# LedMatrix24.net
KiCad netlist of a schematic drawn in EAGLE
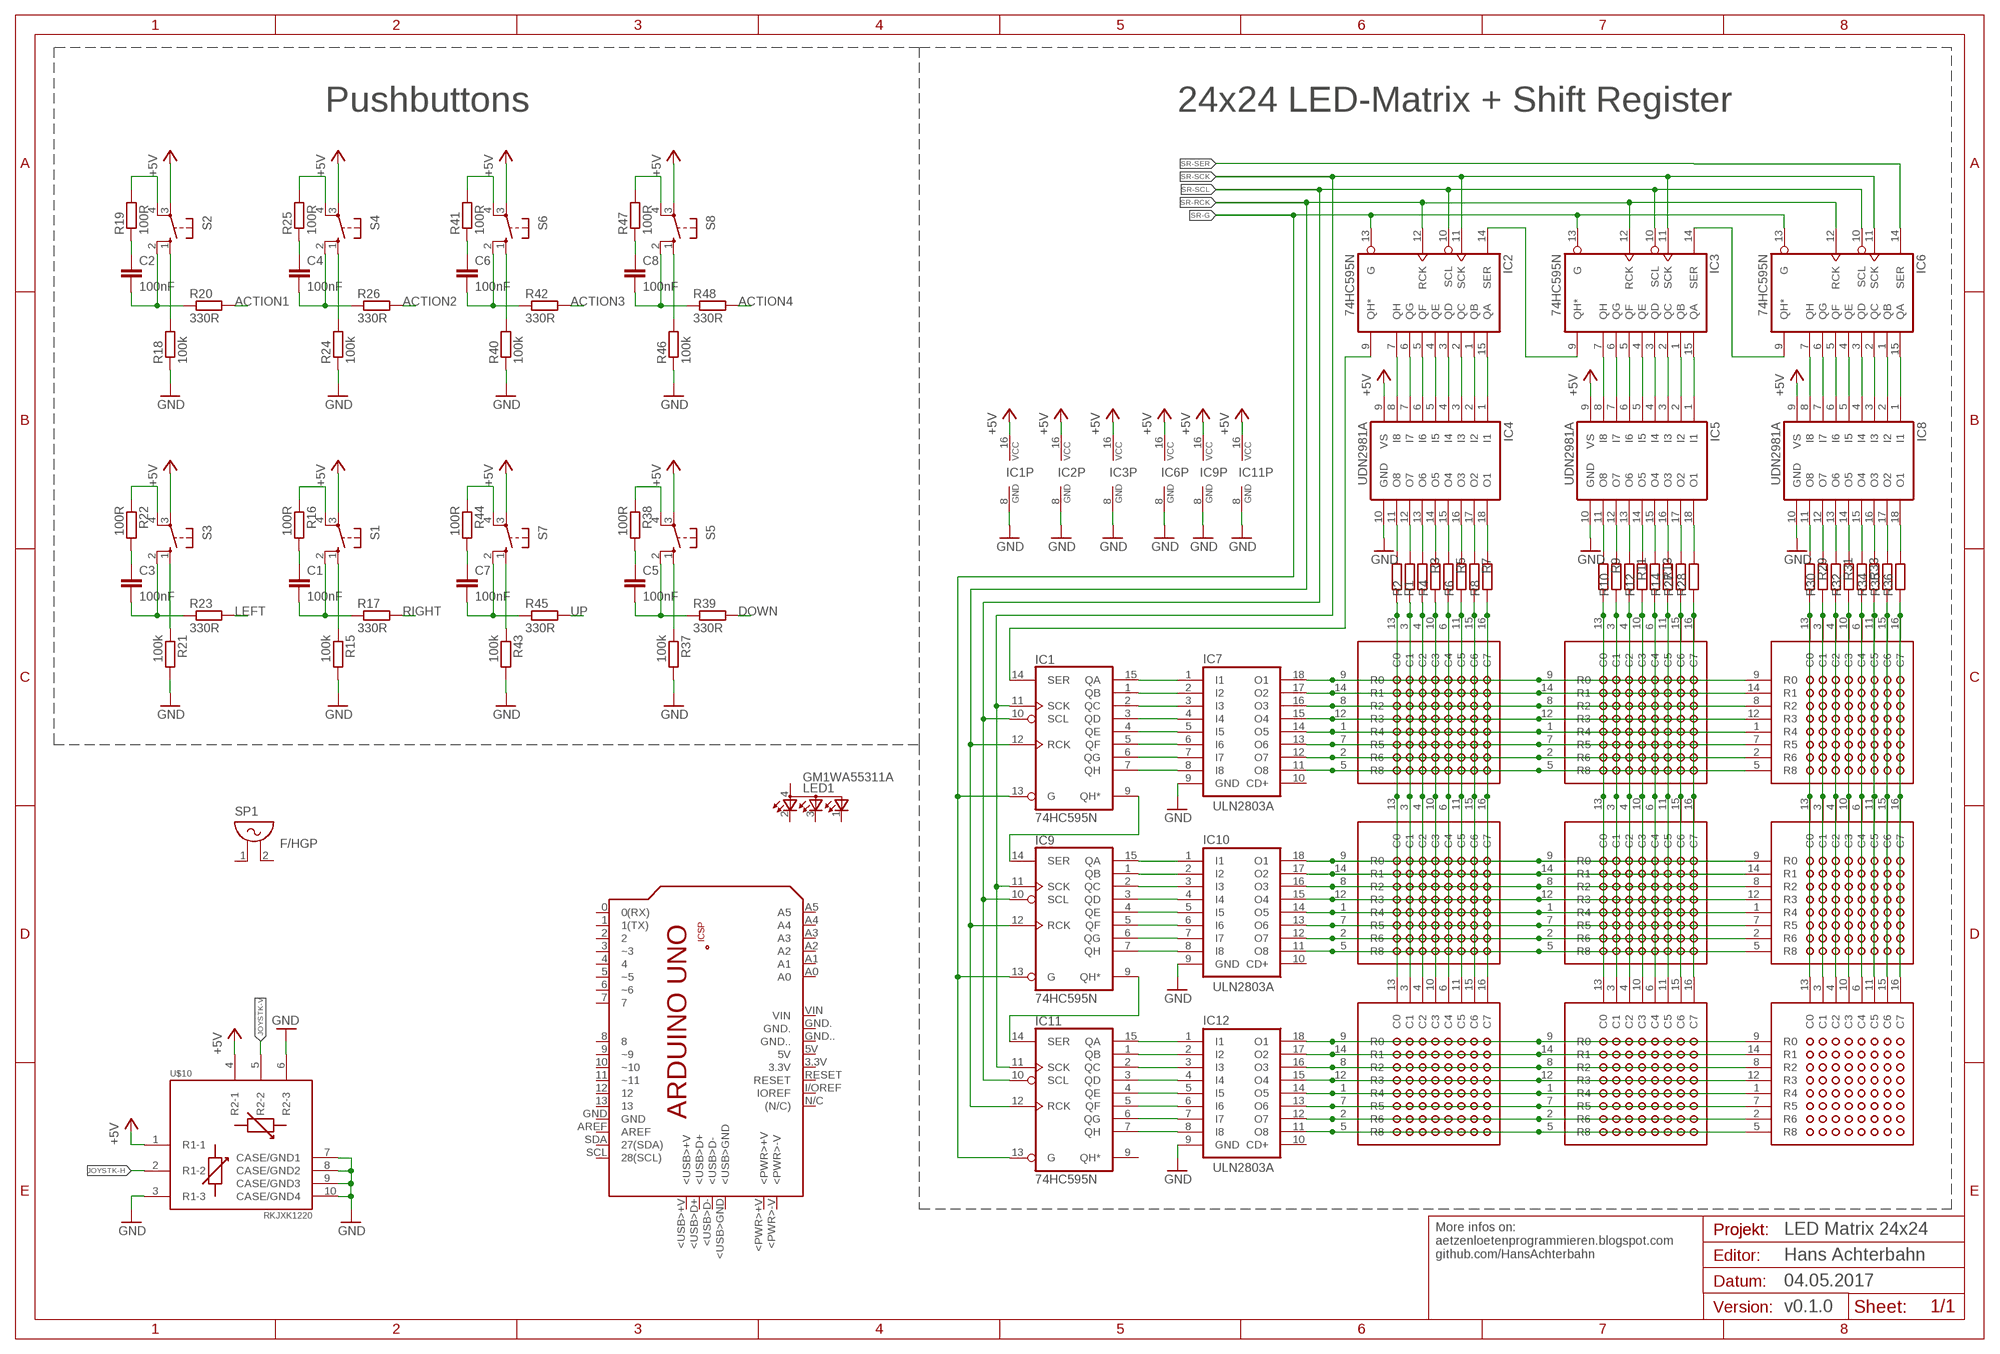
[diagram p0: schematic, sheet 1]

(export (version "E")
  (design (tool "Eeschema 10.0.6"))
  (components
    (comp (ref "C1")
      (value "100nF")
      (footprint "eagle-import:C0805")
      (libsource (lib "eagle-import") (part "C-EUC0805"))
    )
    (comp (ref "C2")
      (value "100nF")
      (footprint "eagle-import:C0805")
      (libsource (lib "eagle-import") (part "C-EUC0805"))
    )
    (comp (ref "C3")
      (value "100nF")
      (footprint "eagle-import:C0805")
      (libsource (lib "eagle-import") (part "C-EUC0805"))
    )
    (comp (ref "C4")
      (value "100nF")
      (footprint "eagle-import:C0805")
      (libsource (lib "eagle-import") (part "C-EUC0805"))
    )
    (comp (ref "C5")
      (value "100nF")
      (footprint "eagle-import:C0805")
      (libsource (lib "eagle-import") (part "C-EUC0805"))
    )
    (comp (ref "C6")
      (value "100nF")
      (footprint "eagle-import:C0805")
      (libsource (lib "eagle-import") (part "C-EUC0805"))
    )
    (comp (ref "C7")
      (value "100nF")
      (footprint "eagle-import:C0805")
      (libsource (lib "eagle-import") (part "C-EUC0805"))
    )
    (comp (ref "C8")
      (value "100nF")
      (footprint "eagle-import:C0805")
      (libsource (lib "eagle-import") (part "C-EUC0805"))
    )
    (comp (ref "IC1")
      (value "74HC595N")
      (footprint "eagle-import:DIL16")
      (libsource (lib "eagle-import") (part "74595NHC"))
    )
    (comp (ref "IC2")
      (value "74HC595N")
      (footprint "eagle-import:DIL16")
      (libsource (lib "eagle-import") (part "74595NHC"))
    )
    (comp (ref "IC3")
      (value "74HC595N")
      (footprint "eagle-import:DIL16")
      (libsource (lib "eagle-import") (part "74595NHC"))
    )
    (comp (ref "IC4")
      (value "UDN2981A")
      (footprint "eagle-import:DIL18")
      (libsource (lib "eagle-import") (part "UDN298A1"))
    )
    (comp (ref "IC5")
      (value "UDN2981A")
      (footprint "eagle-import:DIL18")
      (libsource (lib "eagle-import") (part "UDN298A1"))
    )
    (comp (ref "IC6")
      (value "74HC595N")
      (footprint "eagle-import:DIL16")
      (libsource (lib "eagle-import") (part "74595NHC"))
    )
    (comp (ref "IC7")
      (value "ULN2803A")
      (footprint "eagle-import:DIL18")
      (libsource (lib "eagle-import") (part "ULN2803A"))
    )
    (comp (ref "IC8")
      (value "UDN2981A")
      (footprint "eagle-import:DIL18")
      (libsource (lib "eagle-import") (part "UDN298A1"))
    )
    (comp (ref "IC9")
      (value "74HC595N")
      (footprint "eagle-import:DIL16")
      (libsource (lib "eagle-import") (part "74595NHC"))
    )
    (comp (ref "IC10")
      (value "ULN2803A")
      (footprint "eagle-import:DIL18")
      (libsource (lib "eagle-import") (part "ULN2803A"))
    )
    (comp (ref "IC11")
      (value "74HC595N")
      (footprint "eagle-import:DIL16")
      (libsource (lib "eagle-import") (part "74595NHC"))
    )
    (comp (ref "IC12")
      (value "ULN2803A")
      (footprint "eagle-import:DIL18")
      (libsource (lib "eagle-import") (part "ULN2803A"))
    )
    (comp (ref "LED1")
      (value "GM1WA55311A")
      (footprint "eagle-import:GM1WA55311A")
      (libsource (lib "eagle-import") (part "GM1WA55311A"))
    )
    (comp (ref "PCB1")
      (value "ARDUINO_UNO")
      (footprint "eagle-import:ARDUINO_UNO")
      (libsource (lib "eagle-import") (part "ARDUINO_UNO"))
    )
    (comp (ref "R1")
      (value "R-EU_0207/10")
      (footprint "eagle-import:0207_10")
      (libsource (lib "eagle-import") (part "R-EU_0207/10"))
    )
    (comp (ref "R2")
      (value "R-EU_0207/10")
      (footprint "eagle-import:0207_10")
      (libsource (lib "eagle-import") (part "R-EU_0207/10"))
    )
    (comp (ref "R3")
      (value "R-EU_0207/10")
      (footprint "eagle-import:0207_10")
      (libsource (lib "eagle-import") (part "R-EU_0207/10"))
    )
    (comp (ref "R4")
      (value "R-EU_0207/10")
      (footprint "eagle-import:0207_10")
      (libsource (lib "eagle-import") (part "R-EU_0207/10"))
    )
    (comp (ref "R5")
      (value "R-EU_0207/10")
      (footprint "eagle-import:0207_10")
      (libsource (lib "eagle-import") (part "R-EU_0207/10"))
    )
    (comp (ref "R6")
      (value "R-EU_0207/10")
      (footprint "eagle-import:0207_10")
      (libsource (lib "eagle-import") (part "R-EU_0207/10"))
    )
    (comp (ref "R7")
      (value "R-EU_0207/10")
      (footprint "eagle-import:0207_10")
      (libsource (lib "eagle-import") (part "R-EU_0207/10"))
    )
    (comp (ref "R8")
      (value "R-EU_0207/10")
      (footprint "eagle-import:0207_10")
      (libsource (lib "eagle-import") (part "R-EU_0207/10"))
    )
    (comp (ref "R9")
      (value "R-EU_0207/10")
      (footprint "eagle-import:0207_10")
      (libsource (lib "eagle-import") (part "R-EU_0207/10"))
    )
    (comp (ref "R10")
      (value "R-EU_0207/10")
      (footprint "eagle-import:0207_10")
      (libsource (lib "eagle-import") (part "R-EU_0207/10"))
    )
    (comp (ref "R11")
      (value "R-EU_0207/10")
      (footprint "eagle-import:0207_10")
      (libsource (lib "eagle-import") (part "R-EU_0207/10"))
    )
    (comp (ref "R12")
      (value "R-EU_0207/10")
      (footprint "eagle-import:0207_10")
      (libsource (lib "eagle-import") (part "R-EU_0207/10"))
    )
    (comp (ref "R13")
      (value "R-EU_0207/10")
      (footprint "eagle-import:0207_10")
      (libsource (lib "eagle-import") (part "R-EU_0207/10"))
    )
    (comp (ref "R14")
      (value "R-EU_0207/10")
      (footprint "eagle-import:0207_10")
      (libsource (lib "eagle-import") (part "R-EU_0207/10"))
    )
    (comp (ref "R15")
      (value "100k")
      (footprint "eagle-import:R0603")
      (libsource (lib "eagle-import") (part "R-EU_R0603"))
    )
    (comp (ref "R16")
      (value "100R")
      (footprint "eagle-import:R0603")
      (libsource (lib "eagle-import") (part "R-EU_R0603"))
    )
    (comp (ref "R17")
      (value "330R")
      (footprint "eagle-import:R0603")
      (libsource (lib "eagle-import") (part "R-EU_R0603"))
    )
    (comp (ref "R18")
      (value "100k")
      (footprint "eagle-import:R0603")
      (libsource (lib "eagle-import") (part "R-EU_R0603"))
    )
    (comp (ref "R19")
      (value "100R")
      (footprint "eagle-import:R0603")
      (libsource (lib "eagle-import") (part "R-EU_R0603"))
    )
    (comp (ref "R20")
      (value "330R")
      (footprint "eagle-import:R0603")
      (libsource (lib "eagle-import") (part "R-EU_R0603"))
    )
    (comp (ref "R21")
      (value "100k")
      (footprint "eagle-import:R0603")
      (libsource (lib "eagle-import") (part "R-EU_R0603"))
    )
    (comp (ref "R22")
      (value "100R")
      (footprint "eagle-import:R0603")
      (libsource (lib "eagle-import") (part "R-EU_R0603"))
    )
    (comp (ref "R23")
      (value "330R")
      (footprint "eagle-import:R0603")
      (libsource (lib "eagle-import") (part "R-EU_R0603"))
    )
    (comp (ref "R24")
      (value "100k")
      (footprint "eagle-import:R0603")
      (libsource (lib "eagle-import") (part "R-EU_R0603"))
    )
    (comp (ref "R25")
      (value "100R")
      (footprint "eagle-import:R0603")
      (libsource (lib "eagle-import") (part "R-EU_R0603"))
    )
    (comp (ref "R26")
      (value "330R")
      (footprint "eagle-import:R0603")
      (libsource (lib "eagle-import") (part "R-EU_R0603"))
    )
    (comp (ref "R27")
      (value "R-EU_0207/10")
      (footprint "eagle-import:0207_10")
      (libsource (lib "eagle-import") (part "R-EU_0207/10"))
    )
    (comp (ref "R28")
      (value "R-EU_0207/10")
      (footprint "eagle-import:0207_10")
      (libsource (lib "eagle-import") (part "R-EU_0207/10"))
    )
    (comp (ref "R29")
      (value "R-EU_0207/10")
      (footprint "eagle-import:0207_10")
      (libsource (lib "eagle-import") (part "R-EU_0207/10"))
    )
    (comp (ref "R30")
      (value "R-EU_0207/10")
      (footprint "eagle-import:0207_10")
      (libsource (lib "eagle-import") (part "R-EU_0207/10"))
    )
    (comp (ref "R31")
      (value "R-EU_0207/10")
      (footprint "eagle-import:0207_10")
      (libsource (lib "eagle-import") (part "R-EU_0207/10"))
    )
    (comp (ref "R32")
      (value "R-EU_0207/10")
      (footprint "eagle-import:0207_10")
      (libsource (lib "eagle-import") (part "R-EU_0207/10"))
    )
    (comp (ref "R33")
      (value "R-EU_0207/10")
      (footprint "eagle-import:0207_10")
      (libsource (lib "eagle-import") (part "R-EU_0207/10"))
    )
    (comp (ref "R34")
      (value "R-EU_0207/10")
      (footprint "eagle-import:0207_10")
      (libsource (lib "eagle-import") (part "R-EU_0207/10"))
    )
    (comp (ref "R35")
      (value "R-EU_0207/10")
      (footprint "eagle-import:0207_10")
      (libsource (lib "eagle-import") (part "R-EU_0207/10"))
    )
    (comp (ref "R36")
      (value "R-EU_0207/10")
      (footprint "eagle-import:0207_10")
      (libsource (lib "eagle-import") (part "R-EU_0207/10"))
    )
    (comp (ref "R37")
      (value "100k")
      (footprint "eagle-import:R0603")
      (libsource (lib "eagle-import") (part "R-EU_R0603"))
    )
    (comp (ref "R38")
      (value "100R")
      (footprint "eagle-import:R0603")
      (libsource (lib "eagle-import") (part "R-EU_R0603"))
    )
    (comp (ref "R39")
      (value "330R")
      (footprint "eagle-import:R0603")
      (libsource (lib "eagle-import") (part "R-EU_R0603"))
    )
    (comp (ref "R40")
      (value "100k")
      (footprint "eagle-import:R0603")
      (libsource (lib "eagle-import") (part "R-EU_R0603"))
    )
    (comp (ref "R41")
      (value "100R")
      (footprint "eagle-import:R0603")
      (libsource (lib "eagle-import") (part "R-EU_R0603"))
    )
    (comp (ref "R42")
      (value "330R")
      (footprint "eagle-import:R0603")
      (libsource (lib "eagle-import") (part "R-EU_R0603"))
    )
    (comp (ref "R43")
      (value "100k")
      (footprint "eagle-import:R0603")
      (libsource (lib "eagle-import") (part "R-EU_R0603"))
    )
    (comp (ref "R44")
      (value "100R")
      (footprint "eagle-import:R0603")
      (libsource (lib "eagle-import") (part "R-EU_R0603"))
    )
    (comp (ref "R45")
      (value "330R")
      (footprint "eagle-import:R0603")
      (libsource (lib "eagle-import") (part "R-EU_R0603"))
    )
    (comp (ref "R46")
      (value "100k")
      (footprint "eagle-import:R0603")
      (libsource (lib "eagle-import") (part "R-EU_R0603"))
    )
    (comp (ref "R47")
      (value "100R")
      (footprint "eagle-import:R0603")
      (libsource (lib "eagle-import") (part "R-EU_R0603"))
    )
    (comp (ref "R48")
      (value "330R")
      (footprint "eagle-import:R0603")
      (libsource (lib "eagle-import") (part "R-EU_R0603"))
    )
    (comp (ref "S1")
      (value "10-XX")
      (footprint "eagle-import:B3F-10XX")
      (libsource (lib "eagle-import") (part "10-XX"))
    )
    (comp (ref "S2")
      (value "10-XX")
      (footprint "eagle-import:B3F-10XX")
      (libsource (lib "eagle-import") (part "10-XX"))
    )
    (comp (ref "S3")
      (value "10-XX")
      (footprint "eagle-import:B3F-10XX")
      (libsource (lib "eagle-import") (part "10-XX"))
    )
    (comp (ref "S4")
      (value "10-XX")
      (footprint "eagle-import:B3F-10XX")
      (libsource (lib "eagle-import") (part "10-XX"))
    )
    (comp (ref "S5")
      (value "10-XX")
      (footprint "eagle-import:B3F-10XX")
      (libsource (lib "eagle-import") (part "10-XX"))
    )
    (comp (ref "S6")
      (value "10-XX")
      (footprint "eagle-import:B3F-10XX")
      (libsource (lib "eagle-import") (part "10-XX"))
    )
    (comp (ref "S7")
      (value "10-XX")
      (footprint "eagle-import:B3F-10XX")
      (libsource (lib "eagle-import") (part "10-XX"))
    )
    (comp (ref "S8")
      (value "10-XX")
      (footprint "eagle-import:B3F-10XX")
      (libsource (lib "eagle-import") (part "10-XX"))
    )
    (comp (ref "SP1")
      (value "F/HGP")
      (footprint "eagle-import:F_HGP")
      (libsource (lib "eagle-import") (part "F/HGP"))
    )
    (comp (ref "U$1")
      (value "TOP-CA-788BS")
      (footprint "eagle-import:TOP-CA-788BS")
      (libsource (lib "eagle-import") (part "TOP-CA-788BS"))
    )
    (comp (ref "U$2")
      (value "TOP-CA-788BS")
      (footprint "eagle-import:TOP-CA-788BS")
      (libsource (lib "eagle-import") (part "TOP-CA-788BS"))
    )
    (comp (ref "U$3")
      (value "TOP-CA-788BS")
      (footprint "eagle-import:TOP-CA-788BS")
      (libsource (lib "eagle-import") (part "TOP-CA-788BS"))
    )
    (comp (ref "U$4")
      (value "TOP-CA-788BS")
      (footprint "eagle-import:TOP-CA-788BS")
      (libsource (lib "eagle-import") (part "TOP-CA-788BS"))
    )
    (comp (ref "U$5")
      (value "TOP-CA-788BS")
      (footprint "eagle-import:TOP-CA-788BS")
      (libsource (lib "eagle-import") (part "TOP-CA-788BS"))
    )
    (comp (ref "U$6")
      (value "TOP-CA-788BS")
      (footprint "eagle-import:TOP-CA-788BS")
      (libsource (lib "eagle-import") (part "TOP-CA-788BS"))
    )
    (comp (ref "U$7")
      (value "TOP-CA-788BS")
      (footprint "eagle-import:TOP-CA-788BS")
      (libsource (lib "eagle-import") (part "TOP-CA-788BS"))
    )
    (comp (ref "U$8")
      (value "TOP-CA-788BS")
      (footprint "eagle-import:TOP-CA-788BS")
      (libsource (lib "eagle-import") (part "TOP-CA-788BS"))
    )
    (comp (ref "U$9")
      (value "TOP-CA-788BS")
      (footprint "eagle-import:TOP-CA-788BS")
      (libsource (lib "eagle-import") (part "TOP-CA-788BS"))
    )
    (comp (ref "U$10")
      (value "RKJXK1220")
      (footprint "eagle-import:RKJXK1220")
      (libsource (lib "eagle-import") (part "RKJXK1220"))
    )
  )
  (nets
    (net (code "1") (name "+5V") (class "Default")
      (node (ref "IC1") (pin "16") (pinfunction "VCC_16") (pintype "power_in"))
      (node (ref "IC11") (pin "16") (pinfunction "VCC_16") (pintype "power_in"))
      (node (ref "IC2") (pin "16") (pinfunction "VCC_16") (pintype "power_in"))
      (node (ref "IC3") (pin "16") (pinfunction "VCC_16") (pintype "power_in"))
      (node (ref "IC4") (pin "9") (pinfunction "VS_9") (pintype "passive"))
      (node (ref "IC5") (pin "9") (pinfunction "VS_9") (pintype "passive"))
      (node (ref "IC6") (pin "16") (pinfunction "VCC_16") (pintype "power_in"))
      (node (ref "IC8") (pin "9") (pinfunction "VS_9") (pintype "passive"))
      (node (ref "IC9") (pin "16") (pinfunction "VCC_16") (pintype "power_in"))
      (node (ref "S1") (pin "3") (pinfunction "P_3") (pintype "passive"))
      (node (ref "S2") (pin "3") (pinfunction "P_3") (pintype "passive"))
      (node (ref "S3") (pin "3") (pinfunction "P_3") (pintype "passive"))
      (node (ref "S4") (pin "3") (pinfunction "P_3") (pintype "passive"))
      (node (ref "S5") (pin "3") (pinfunction "P_3") (pintype "passive"))
      (node (ref "S6") (pin "3") (pinfunction "P_3") (pintype "passive"))
      (node (ref "S7") (pin "3") (pinfunction "P_3") (pintype "passive"))
      (node (ref "S8") (pin "3") (pinfunction "P_3") (pintype "passive"))
      (node (ref "U$10") (pin "1") (pinfunction "R1-1_1") (pintype "bidirectional"))
      (node (ref "U$10") (pin "4") (pinfunction "R2-1_4") (pintype "bidirectional"))
    )
    (net (code "2") (name "/ACTION1") (class "Default")
      (node (ref "R20") (pin "2") (pinfunction "2_2") (pintype "passive"))
    )
    (net (code "3") (name "/ACTION2") (class "Default")
      (node (ref "R26") (pin "2") (pinfunction "2_2") (pintype "passive"))
    )
    (net (code "4") (name "/ACTION3") (class "Default")
      (node (ref "R42") (pin "2") (pinfunction "2_2") (pintype "passive"))
    )
    (net (code "5") (name "/ACTION4") (class "Default")
      (node (ref "R48") (pin "2") (pinfunction "2_2") (pintype "passive"))
    )
    (net (code "6") (name "/DOWN") (class "Default")
      (node (ref "R39") (pin "2") (pinfunction "2_2") (pintype "passive"))
    )
    (net (code "7") (name "/LEFT") (class "Default")
      (node (ref "R23") (pin "2") (pinfunction "2_2") (pintype "passive"))
    )
    (net (code "8") (name "/N$53") (class "Default")
      (node (ref "R1") (pin "1") (pinfunction "1_1") (pintype "passive"))
      (node (ref "R2") (pin "1") (pinfunction "1_1") (pintype "passive"))
      (node (ref "U$1") (pin "13") (pinfunction "C0_13") (pintype "bidirectional"))
      (node (ref "U$1") (pin "3") (pinfunction "C1_3") (pintype "bidirectional"))
      (node (ref "U$4") (pin "13") (pinfunction "C0_13") (pintype "bidirectional"))
      (node (ref "U$4") (pin "3") (pinfunction "C1_3") (pintype "bidirectional"))
      (node (ref "U$7") (pin "13") (pinfunction "C0_13") (pintype "bidirectional"))
      (node (ref "U$7") (pin "3") (pinfunction "C1_3") (pintype "bidirectional"))
    )
    (net (code "9") (name "/RIGHT") (class "Default")
      (node (ref "R17") (pin "2") (pinfunction "2_2") (pintype "passive"))
    )
    (net (code "10") (name "/UP") (class "Default")
      (node (ref "R45") (pin "2") (pinfunction "2_2") (pintype "passive"))
    )
    (net (code "11") (name "GND") (class "Default")
      (node (ref "IC1") (pin "8") (pinfunction "GND_8") (pintype "power_in"))
      (node (ref "IC10") (pin "9") (pinfunction "GND_9") (pintype "power_in"))
      (node (ref "IC11") (pin "8") (pinfunction "GND_8") (pintype "power_in"))
      (node (ref "IC12") (pin "9") (pinfunction "GND_9") (pintype "power_in"))
      (node (ref "IC2") (pin "8") (pinfunction "GND_8") (pintype "power_in"))
      (node (ref "IC3") (pin "8") (pinfunction "GND_8") (pintype "power_in"))
      (node (ref "IC4") (pin "10") (pinfunction "GND_10") (pintype "power_in"))
      (node (ref "IC5") (pin "10") (pinfunction "GND_10") (pintype "power_in"))
      (node (ref "IC6") (pin "8") (pinfunction "GND_8") (pintype "power_in"))
      (node (ref "IC7") (pin "9") (pinfunction "GND_9") (pintype "power_in"))
      (node (ref "IC8") (pin "10") (pinfunction "GND_10") (pintype "power_in"))
      (node (ref "IC9") (pin "8") (pinfunction "GND_8") (pintype "power_in"))
      (node (ref "R15") (pin "2") (pinfunction "2_2") (pintype "passive"))
      (node (ref "R18") (pin "1") (pinfunction "1_1") (pintype "passive"))
      (node (ref "R21") (pin "2") (pinfunction "2_2") (pintype "passive"))
      (node (ref "R24") (pin "1") (pinfunction "1_1") (pintype "passive"))
      (node (ref "R37") (pin "2") (pinfunction "2_2") (pintype "passive"))
      (node (ref "R40") (pin "1") (pinfunction "1_1") (pintype "passive"))
      (node (ref "R43") (pin "2") (pinfunction "2_2") (pintype "passive"))
      (node (ref "R46") (pin "1") (pinfunction "1_1") (pintype "passive"))
      (node (ref "U$10") (pin "10") (pinfunction "CASE/GND4_10") (pintype "bidirectional"))
      (node (ref "U$10") (pin "3") (pinfunction "R1-3_3") (pintype "bidirectional"))
      (node (ref "U$10") (pin "6") (pinfunction "R2-3_6") (pintype "bidirectional"))
      (node (ref "U$10") (pin "7") (pinfunction "CASE/GND1_7") (pintype "bidirectional"))
      (node (ref "U$10") (pin "8") (pinfunction "CASE/GND2_8") (pintype "bidirectional"))
      (node (ref "U$10") (pin "9") (pinfunction "CASE/GND3_9") (pintype "bidirectional"))
    )
    (net (code "12") (name "JOYSTK-H") (class "Default")
      (node (ref "U$10") (pin "2") (pinfunction "R1-2_2") (pintype "bidirectional"))
    )
    (net (code "13") (name "JOYSTK-V") (class "Default")
      (node (ref "U$10") (pin "5") (pinfunction "R2-2_5") (pintype "bidirectional"))
    )
    (net (code "14") (name "Net-(C1-Pad1)") (class "Default")
      (node (ref "C1") (pin "1") (pinfunction "1_1") (pintype "passive"))
      (node (ref "R16") (pin "2") (pinfunction "2_2") (pintype "passive"))
    )
    (net (code "15") (name "Net-(C2-Pad1)") (class "Default")
      (node (ref "C2") (pin "1") (pinfunction "1_1") (pintype "passive"))
      (node (ref "R19") (pin "1") (pinfunction "1_1") (pintype "passive"))
    )
    (net (code "16") (name "Net-(C3-Pad1)") (class "Default")
      (node (ref "C3") (pin "1") (pinfunction "1_1") (pintype "passive"))
      (node (ref "R22") (pin "2") (pinfunction "2_2") (pintype "passive"))
    )
    (net (code "17") (name "Net-(C4-Pad1)") (class "Default")
      (node (ref "C4") (pin "1") (pinfunction "1_1") (pintype "passive"))
      (node (ref "R25") (pin "1") (pinfunction "1_1") (pintype "passive"))
    )
    (net (code "18") (name "Net-(C5-Pad1)") (class "Default")
      (node (ref "C5") (pin "1") (pinfunction "1_1") (pintype "passive"))
      (node (ref "R38") (pin "2") (pinfunction "2_2") (pintype "passive"))
    )
    (net (code "19") (name "Net-(C6-Pad1)") (class "Default")
      (node (ref "C6") (pin "1") (pinfunction "1_1") (pintype "passive"))
      (node (ref "R41") (pin "1") (pinfunction "1_1") (pintype "passive"))
    )
    (net (code "20") (name "Net-(C7-Pad1)") (class "Default")
      (node (ref "C7") (pin "1") (pinfunction "1_1") (pintype "passive"))
      (node (ref "R44") (pin "2") (pinfunction "2_2") (pintype "passive"))
    )
    (net (code "21") (name "Net-(C8-Pad1)") (class "Default")
      (node (ref "C8") (pin "1") (pinfunction "1_1") (pintype "passive"))
      (node (ref "R47") (pin "1") (pinfunction "1_1") (pintype "passive"))
    )
    (net (code "22") (name "Net-(IC1A-QA)") (class "Default")
      (node (ref "IC1") (pin "15") (pinfunction "QA_15") (pintype "tri_state"))
      (node (ref "IC7") (pin "1") (pinfunction "I1_1") (pintype "input"))
    )
    (net (code "23") (name "Net-(IC1A-QB)") (class "Default")
      (node (ref "IC1") (pin "1") (pinfunction "QB_1") (pintype "tri_state"))
      (node (ref "IC7") (pin "2") (pinfunction "I2_2") (pintype "input"))
    )
    (net (code "24") (name "Net-(IC1A-QC)") (class "Default")
      (node (ref "IC1") (pin "2") (pinfunction "QC_2") (pintype "tri_state"))
      (node (ref "IC7") (pin "3") (pinfunction "I3_3") (pintype "input"))
    )
    (net (code "25") (name "Net-(IC1A-QD)") (class "Default")
      (node (ref "IC1") (pin "3") (pinfunction "QD_3") (pintype "tri_state"))
      (node (ref "IC7") (pin "4") (pinfunction "I4_4") (pintype "input"))
    )
    (net (code "26") (name "Net-(IC1A-QE)") (class "Default")
      (node (ref "IC1") (pin "4") (pinfunction "QE_4") (pintype "tri_state"))
      (node (ref "IC7") (pin "5") (pinfunction "I5_5") (pintype "input"))
    )
    (net (code "27") (name "Net-(IC1A-QF)") (class "Default")
      (node (ref "IC1") (pin "5") (pinfunction "QF_5") (pintype "tri_state"))
      (node (ref "IC7") (pin "6") (pinfunction "I6_6") (pintype "input"))
    )
    (net (code "28") (name "Net-(IC1A-QG)") (class "Default")
      (node (ref "IC1") (pin "6") (pinfunction "QG_6") (pintype "tri_state"))
      (node (ref "IC7") (pin "7") (pinfunction "I7_7") (pintype "input"))
    )
    (net (code "29") (name "Net-(IC1A-QH)") (class "Default")
      (node (ref "IC1") (pin "7") (pinfunction "QH_7") (pintype "tri_state"))
      (node (ref "IC7") (pin "8") (pinfunction "I8_8") (pintype "input"))
    )
    (net (code "30") (name "Net-(IC1A-QH*)") (class "Default")
      (node (ref "IC1") (pin "9") (pinfunction "QH*_9") (pintype "tri_state"))
      (node (ref "IC9") (pin "14") (pinfunction "SER_14") (pintype "input"))
    )
    (net (code "31") (name "Net-(IC1A-SER)") (class "Default")
      (node (ref "IC1") (pin "14") (pinfunction "SER_14") (pintype "input"))
      (node (ref "IC2") (pin "9") (pinfunction "QH*_9") (pintype "tri_state"))
    )
    (net (code "32") (name "Net-(IC2A-QA)") (class "Default")
      (node (ref "IC2") (pin "15") (pinfunction "QA_15") (pintype "tri_state"))
      (node (ref "IC4") (pin "1") (pinfunction "I1_1") (pintype "input"))
    )
    (net (code "33") (name "Net-(IC2A-QB)") (class "Default")
      (node (ref "IC2") (pin "1") (pinfunction "QB_1") (pintype "tri_state"))
      (node (ref "IC4") (pin "2") (pinfunction "I2_2") (pintype "input"))
    )
    (net (code "34") (name "Net-(IC2A-QC)") (class "Default")
      (node (ref "IC2") (pin "2") (pinfunction "QC_2") (pintype "tri_state"))
      (node (ref "IC4") (pin "3") (pinfunction "I3_3") (pintype "input"))
    )
    (net (code "35") (name "Net-(IC2A-QD)") (class "Default")
      (node (ref "IC2") (pin "3") (pinfunction "QD_3") (pintype "tri_state"))
      (node (ref "IC4") (pin "4") (pinfunction "I4_4") (pintype "input"))
    )
    (net (code "36") (name "Net-(IC2A-QE)") (class "Default")
      (node (ref "IC2") (pin "4") (pinfunction "QE_4") (pintype "tri_state"))
      (node (ref "IC4") (pin "5") (pinfunction "I5_5") (pintype "input"))
    )
    (net (code "37") (name "Net-(IC2A-QF)") (class "Default")
      (node (ref "IC2") (pin "5") (pinfunction "QF_5") (pintype "tri_state"))
      (node (ref "IC4") (pin "6") (pinfunction "I6_6") (pintype "input"))
    )
    (net (code "38") (name "Net-(IC2A-QG)") (class "Default")
      (node (ref "IC2") (pin "6") (pinfunction "QG_6") (pintype "tri_state"))
      (node (ref "IC4") (pin "7") (pinfunction "I7_7") (pintype "input"))
    )
    (net (code "39") (name "Net-(IC2A-QH)") (class "Default")
      (node (ref "IC2") (pin "7") (pinfunction "QH_7") (pintype "tri_state"))
      (node (ref "IC4") (pin "8") (pinfunction "I8_8") (pintype "input"))
    )
    (net (code "40") (name "Net-(IC2A-SER)") (class "Default")
      (node (ref "IC2") (pin "14") (pinfunction "SER_14") (pintype "input"))
      (node (ref "IC3") (pin "9") (pinfunction "QH*_9") (pintype "tri_state"))
    )
    (net (code "41") (name "Net-(IC3A-QA)") (class "Default")
      (node (ref "IC3") (pin "15") (pinfunction "QA_15") (pintype "tri_state"))
      (node (ref "IC5") (pin "1") (pinfunction "I1_1") (pintype "input"))
    )
    (net (code "42") (name "Net-(IC3A-QB)") (class "Default")
      (node (ref "IC3") (pin "1") (pinfunction "QB_1") (pintype "tri_state"))
      (node (ref "IC5") (pin "2") (pinfunction "I2_2") (pintype "input"))
    )
    (net (code "43") (name "Net-(IC3A-QC)") (class "Default")
      (node (ref "IC3") (pin "2") (pinfunction "QC_2") (pintype "tri_state"))
      (node (ref "IC5") (pin "3") (pinfunction "I3_3") (pintype "input"))
    )
    (net (code "44") (name "Net-(IC3A-QD)") (class "Default")
      (node (ref "IC3") (pin "3") (pinfunction "QD_3") (pintype "tri_state"))
      (node (ref "IC5") (pin "4") (pinfunction "I4_4") (pintype "input"))
    )
    (net (code "45") (name "Net-(IC3A-QE)") (class "Default")
      (node (ref "IC3") (pin "4") (pinfunction "QE_4") (pintype "tri_state"))
      (node (ref "IC5") (pin "5") (pinfunction "I5_5") (pintype "input"))
    )
    (net (code "46") (name "Net-(IC3A-QF)") (class "Default")
      (node (ref "IC3") (pin "5") (pinfunction "QF_5") (pintype "tri_state"))
      (node (ref "IC5") (pin "6") (pinfunction "I6_6") (pintype "input"))
    )
    (net (code "47") (name "Net-(IC3A-QG)") (class "Default")
      (node (ref "IC3") (pin "6") (pinfunction "QG_6") (pintype "tri_state"))
      (node (ref "IC5") (pin "7") (pinfunction "I7_7") (pintype "input"))
    )
    (net (code "48") (name "Net-(IC3A-QH)") (class "Default")
      (node (ref "IC3") (pin "7") (pinfunction "QH_7") (pintype "tri_state"))
      (node (ref "IC5") (pin "8") (pinfunction "I8_8") (pintype "input"))
    )
    (net (code "49") (name "Net-(IC3A-SER)") (class "Default")
      (node (ref "IC3") (pin "14") (pinfunction "SER_14") (pintype "input"))
      (node (ref "IC6") (pin "9") (pinfunction "QH*_9") (pintype "tri_state"))
    )
    (net (code "50") (name "Net-(IC4-O1)") (class "Default")
      (node (ref "IC4") (pin "18") (pinfunction "O1_18") (pintype "open_collector"))
      (node (ref "R8") (pin "2") (pinfunction "2_2") (pintype "passive"))
    )
    (net (code "51") (name "Net-(IC4-O2)") (class "Default")
      (node (ref "IC4") (pin "17") (pinfunction "O2_17") (pintype "open_collector"))
      (node (ref "R7") (pin "1") (pinfunction "1_1") (pintype "passive"))
    )
    (net (code "52") (name "Net-(IC4-O3)") (class "Default")
      (node (ref "IC4") (pin "16") (pinfunction "O3_16") (pintype "open_collector"))
      (node (ref "R6") (pin "2") (pinfunction "2_2") (pintype "passive"))
    )
    (net (code "53") (name "Net-(IC4-O4)") (class "Default")
      (node (ref "IC4") (pin "15") (pinfunction "O4_15") (pintype "open_collector"))
      (node (ref "R5") (pin "1") (pinfunction "1_1") (pintype "passive"))
    )
    (net (code "54") (name "Net-(IC4-O5)") (class "Default")
      (node (ref "IC4") (pin "14") (pinfunction "O5_14") (pintype "open_collector"))
      (node (ref "R4") (pin "2") (pinfunction "2_2") (pintype "passive"))
    )
    (net (code "55") (name "Net-(IC4-O6)") (class "Default")
      (node (ref "IC4") (pin "13") (pinfunction "O6_13") (pintype "open_collector"))
      (node (ref "R3") (pin "1") (pinfunction "1_1") (pintype "passive"))
    )
    (net (code "56") (name "Net-(IC4-O7)") (class "Default")
      (node (ref "IC4") (pin "12") (pinfunction "O7_12") (pintype "open_collector"))
      (node (ref "R2") (pin "2") (pinfunction "2_2") (pintype "passive"))
    )
    (net (code "57") (name "Net-(IC4-O8)") (class "Default")
      (node (ref "IC4") (pin "11") (pinfunction "O8_11") (pintype "open_collector"))
      (node (ref "R1") (pin "2") (pinfunction "2_2") (pintype "passive"))
    )
    (net (code "58") (name "Net-(IC5-O1)") (class "Default")
      (node (ref "IC5") (pin "18") (pinfunction "O1_18") (pintype "open_collector"))
      (node (ref "R28") (pin "2") (pinfunction "2_2") (pintype "passive"))
    )
    (net (code "59") (name "Net-(IC5-O2)") (class "Default")
      (node (ref "IC5") (pin "17") (pinfunction "O2_17") (pintype "open_collector"))
      (node (ref "R27") (pin "2") (pinfunction "2_2") (pintype "passive"))
    )
    (net (code "60") (name "Net-(IC5-O3)") (class "Default")
      (node (ref "IC5") (pin "16") (pinfunction "O3_16") (pintype "open_collector"))
      (node (ref "R14") (pin "2") (pinfunction "2_2") (pintype "passive"))
    )
    (net (code "61") (name "Net-(IC5-O4)") (class "Default")
      (node (ref "IC5") (pin "15") (pinfunction "O4_15") (pintype "open_collector"))
      (node (ref "R13") (pin "1") (pinfunction "1_1") (pintype "passive"))
    )
    (net (code "62") (name "Net-(IC5-O5)") (class "Default")
      (node (ref "IC5") (pin "14") (pinfunction "O5_14") (pintype "open_collector"))
      (node (ref "R12") (pin "2") (pinfunction "2_2") (pintype "passive"))
    )
    (net (code "63") (name "Net-(IC5-O6)") (class "Default")
      (node (ref "IC5") (pin "13") (pinfunction "O6_13") (pintype "open_collector"))
      (node (ref "R11") (pin "1") (pinfunction "1_1") (pintype "passive"))
    )
    (net (code "64") (name "Net-(IC5-O7)") (class "Default")
      (node (ref "IC5") (pin "12") (pinfunction "O7_12") (pintype "open_collector"))
      (node (ref "R10") (pin "2") (pinfunction "2_2") (pintype "passive"))
    )
    (net (code "65") (name "Net-(IC5-O8)") (class "Default")
      (node (ref "IC5") (pin "11") (pinfunction "O8_11") (pintype "open_collector"))
      (node (ref "R9") (pin "1") (pinfunction "1_1") (pintype "passive"))
    )
    (net (code "66") (name "Net-(IC6A-QA)") (class "Default")
      (node (ref "IC6") (pin "15") (pinfunction "QA_15") (pintype "tri_state"))
      (node (ref "IC8") (pin "1") (pinfunction "I1_1") (pintype "input"))
    )
    (net (code "67") (name "Net-(IC6A-QB)") (class "Default")
      (node (ref "IC6") (pin "1") (pinfunction "QB_1") (pintype "tri_state"))
      (node (ref "IC8") (pin "2") (pinfunction "I2_2") (pintype "input"))
    )
    (net (code "68") (name "Net-(IC6A-QC)") (class "Default")
      (node (ref "IC6") (pin "2") (pinfunction "QC_2") (pintype "tri_state"))
      (node (ref "IC8") (pin "3") (pinfunction "I3_3") (pintype "input"))
    )
    (net (code "69") (name "Net-(IC6A-QD)") (class "Default")
      (node (ref "IC6") (pin "3") (pinfunction "QD_3") (pintype "tri_state"))
      (node (ref "IC8") (pin "4") (pinfunction "I4_4") (pintype "input"))
    )
    (net (code "70") (name "Net-(IC6A-QE)") (class "Default")
      (node (ref "IC6") (pin "4") (pinfunction "QE_4") (pintype "tri_state"))
      (node (ref "IC8") (pin "5") (pinfunction "I5_5") (pintype "input"))
    )
    (net (code "71") (name "Net-(IC6A-QF)") (class "Default")
      (node (ref "IC6") (pin "5") (pinfunction "QF_5") (pintype "tri_state"))
      (node (ref "IC8") (pin "6") (pinfunction "I6_6") (pintype "input"))
    )
    (net (code "72") (name "Net-(IC6A-QG)") (class "Default")
      (node (ref "IC6") (pin "6") (pinfunction "QG_6") (pintype "tri_state"))
      (node (ref "IC8") (pin "7") (pinfunction "I7_7") (pintype "input"))
    )
    (net (code "73") (name "Net-(IC6A-QH)") (class "Default")
      (node (ref "IC6") (pin "7") (pinfunction "QH_7") (pintype "tri_state"))
      (node (ref "IC8") (pin "8") (pinfunction "I8_8") (pintype "input"))
    )
    (net (code "74") (name "Net-(IC7-O1)") (class "Default")
      (node (ref "IC7") (pin "18") (pinfunction "O1_18") (pintype "open_collector"))
      (node (ref "U$1") (pin "9") (pinfunction "R0_9") (pintype "bidirectional"))
      (node (ref "U$2") (pin "9") (pinfunction "R0_9") (pintype "bidirectional"))
      (node (ref "U$3") (pin "9") (pinfunction "R0_9") (pintype "bidirectional"))
    )
    (net (code "75") (name "Net-(IC7-O2)") (class "Default")
      (node (ref "IC7") (pin "17") (pinfunction "O2_17") (pintype "open_collector"))
      (node (ref "U$1") (pin "14") (pinfunction "R1_14") (pintype "bidirectional"))
      (node (ref "U$2") (pin "14") (pinfunction "R1_14") (pintype "bidirectional"))
      (node (ref "U$3") (pin "14") (pinfunction "R1_14") (pintype "bidirectional"))
    )
    (net (code "76") (name "Net-(IC7-O3)") (class "Default")
      (node (ref "IC7") (pin "16") (pinfunction "O3_16") (pintype "open_collector"))
      (node (ref "U$1") (pin "8") (pinfunction "R2_8") (pintype "bidirectional"))
      (node (ref "U$2") (pin "8") (pinfunction "R2_8") (pintype "bidirectional"))
      (node (ref "U$3") (pin "8") (pinfunction "R2_8") (pintype "bidirectional"))
    )
    (net (code "77") (name "Net-(IC7-O4)") (class "Default")
      (node (ref "IC7") (pin "15") (pinfunction "O4_15") (pintype "open_collector"))
      (node (ref "U$1") (pin "12") (pinfunction "R3_12") (pintype "bidirectional"))
      (node (ref "U$2") (pin "12") (pinfunction "R3_12") (pintype "bidirectional"))
      (node (ref "U$3") (pin "12") (pinfunction "R3_12") (pintype "bidirectional"))
    )
    (net (code "78") (name "Net-(IC7-O5)") (class "Default")
      (node (ref "IC7") (pin "14") (pinfunction "O5_14") (pintype "open_collector"))
      (node (ref "U$1") (pin "1") (pinfunction "R4_1") (pintype "bidirectional"))
      (node (ref "U$2") (pin "1") (pinfunction "R4_1") (pintype "bidirectional"))
      (node (ref "U$3") (pin "1") (pinfunction "R4_1") (pintype "bidirectional"))
    )
    (net (code "79") (name "Net-(IC7-O6)") (class "Default")
      (node (ref "IC7") (pin "13") (pinfunction "O6_13") (pintype "open_collector"))
      (node (ref "U$1") (pin "7") (pinfunction "R5_7") (pintype "bidirectional"))
      (node (ref "U$2") (pin "7") (pinfunction "R5_7") (pintype "bidirectional"))
      (node (ref "U$3") (pin "7") (pinfunction "R5_7") (pintype "bidirectional"))
    )
    (net (code "80") (name "Net-(IC7-O7)") (class "Default")
      (node (ref "IC7") (pin "12") (pinfunction "O7_12") (pintype "open_collector"))
      (node (ref "U$1") (pin "2") (pinfunction "R6_2") (pintype "bidirectional"))
      (node (ref "U$2") (pin "2") (pinfunction "R6_2") (pintype "bidirectional"))
      (node (ref "U$3") (pin "2") (pinfunction "R6_2") (pintype "bidirectional"))
    )
    (net (code "81") (name "Net-(IC7-O8)") (class "Default")
      (node (ref "IC7") (pin "11") (pinfunction "O8_11") (pintype "open_collector"))
      (node (ref "U$1") (pin "5") (pinfunction "R8_5") (pintype "bidirectional"))
      (node (ref "U$2") (pin "5") (pinfunction "R8_5") (pintype "bidirectional"))
      (node (ref "U$3") (pin "5") (pinfunction "R8_5") (pintype "bidirectional"))
    )
    (net (code "82") (name "Net-(IC8-O1)") (class "Default")
      (node (ref "IC8") (pin "18") (pinfunction "O1_18") (pintype "open_collector"))
      (node (ref "R36") (pin "2") (pinfunction "2_2") (pintype "passive"))
    )
    (net (code "83") (name "Net-(IC8-O2)") (class "Default")
      (node (ref "IC8") (pin "17") (pinfunction "O2_17") (pintype "open_collector"))
      (node (ref "R35") (pin "2") (pinfunction "2_2") (pintype "passive"))
    )
    (net (code "84") (name "Net-(IC8-O3)") (class "Default")
      (node (ref "IC8") (pin "16") (pinfunction "O3_16") (pintype "open_collector"))
      (node (ref "R34") (pin "2") (pinfunction "2_2") (pintype "passive"))
    )
    (net (code "85") (name "Net-(IC8-O4)") (class "Default")
      (node (ref "IC8") (pin "15") (pinfunction "O4_15") (pintype "open_collector"))
      (node (ref "R33") (pin "1") (pinfunction "1_1") (pintype "passive"))
    )
    (net (code "86") (name "Net-(IC8-O5)") (class "Default")
      (node (ref "IC8") (pin "14") (pinfunction "O5_14") (pintype "open_collector"))
      (node (ref "R32") (pin "2") (pinfunction "2_2") (pintype "passive"))
    )
    (net (code "87") (name "Net-(IC8-O6)") (class "Default")
      (node (ref "IC8") (pin "13") (pinfunction "O6_13") (pintype "open_collector"))
      (node (ref "R31") (pin "1") (pinfunction "1_1") (pintype "passive"))
    )
    (net (code "88") (name "Net-(IC8-O7)") (class "Default")
      (node (ref "IC8") (pin "12") (pinfunction "O7_12") (pintype "open_collector"))
      (node (ref "R30") (pin "2") (pinfunction "2_2") (pintype "passive"))
    )
    (net (code "89") (name "Net-(IC8-O8)") (class "Default")
      (node (ref "IC8") (pin "11") (pinfunction "O8_11") (pintype "open_collector"))
      (node (ref "R29") (pin "1") (pinfunction "1_1") (pintype "passive"))
    )
    (net (code "90") (name "Net-(IC10-I1)") (class "Default")
      (node (ref "IC10") (pin "1") (pinfunction "I1_1") (pintype "input"))
      (node (ref "IC9") (pin "15") (pinfunction "QA_15") (pintype "tri_state"))
    )
    (net (code "91") (name "Net-(IC10-I2)") (class "Default")
      (node (ref "IC10") (pin "2") (pinfunction "I2_2") (pintype "input"))
      (node (ref "IC9") (pin "1") (pinfunction "QB_1") (pintype "tri_state"))
    )
    (net (code "92") (name "Net-(IC10-I3)") (class "Default")
      (node (ref "IC10") (pin "3") (pinfunction "I3_3") (pintype "input"))
      (node (ref "IC9") (pin "2") (pinfunction "QC_2") (pintype "tri_state"))
    )
    (net (code "93") (name "Net-(IC10-I4)") (class "Default")
      (node (ref "IC10") (pin "4") (pinfunction "I4_4") (pintype "input"))
      (node (ref "IC9") (pin "3") (pinfunction "QD_3") (pintype "tri_state"))
    )
    (net (code "94") (name "Net-(IC10-I5)") (class "Default")
      (node (ref "IC10") (pin "5") (pinfunction "I5_5") (pintype "input"))
      (node (ref "IC9") (pin "4") (pinfunction "QE_4") (pintype "tri_state"))
    )
    (net (code "95") (name "Net-(IC10-I6)") (class "Default")
      (node (ref "IC10") (pin "6") (pinfunction "I6_6") (pintype "input"))
      (node (ref "IC9") (pin "5") (pinfunction "QF_5") (pintype "tri_state"))
    )
    (net (code "96") (name "Net-(IC10-I7)") (class "Default")
      (node (ref "IC10") (pin "7") (pinfunction "I7_7") (pintype "input"))
      (node (ref "IC9") (pin "6") (pinfunction "QG_6") (pintype "tri_state"))
    )
    (net (code "97") (name "Net-(IC10-I8)") (class "Default")
      (node (ref "IC10") (pin "8") (pinfunction "I8_8") (pintype "input"))
      (node (ref "IC9") (pin "7") (pinfunction "QH_7") (pintype "tri_state"))
    )
    (net (code "98") (name "Net-(IC10-O1)") (class "Default")
      (node (ref "IC10") (pin "18") (pinfunction "O1_18") (pintype "open_collector"))
      (node (ref "U$4") (pin "9") (pinfunction "R0_9") (pintype "bidirectional"))
      (node (ref "U$5") (pin "9") (pinfunction "R0_9") (pintype "bidirectional"))
      (node (ref "U$6") (pin "9") (pinfunction "R0_9") (pintype "bidirectional"))
    )
    (net (code "99") (name "Net-(IC10-O2)") (class "Default")
      (node (ref "IC10") (pin "17") (pinfunction "O2_17") (pintype "open_collector"))
      (node (ref "U$4") (pin "14") (pinfunction "R1_14") (pintype "bidirectional"))
      (node (ref "U$5") (pin "14") (pinfunction "R1_14") (pintype "bidirectional"))
      (node (ref "U$6") (pin "14") (pinfunction "R1_14") (pintype "bidirectional"))
    )
    (net (code "100") (name "Net-(IC10-O3)") (class "Default")
      (node (ref "IC10") (pin "16") (pinfunction "O3_16") (pintype "open_collector"))
      (node (ref "U$4") (pin "8") (pinfunction "R2_8") (pintype "bidirectional"))
      (node (ref "U$5") (pin "8") (pinfunction "R2_8") (pintype "bidirectional"))
      (node (ref "U$6") (pin "8") (pinfunction "R2_8") (pintype "bidirectional"))
    )
    (net (code "101") (name "Net-(IC10-O4)") (class "Default")
      (node (ref "IC10") (pin "15") (pinfunction "O4_15") (pintype "open_collector"))
      (node (ref "U$4") (pin "12") (pinfunction "R3_12") (pintype "bidirectional"))
      (node (ref "U$5") (pin "12") (pinfunction "R3_12") (pintype "bidirectional"))
      (node (ref "U$6") (pin "12") (pinfunction "R3_12") (pintype "bidirectional"))
    )
    (net (code "102") (name "Net-(IC10-O5)") (class "Default")
      (node (ref "IC10") (pin "14") (pinfunction "O5_14") (pintype "open_collector"))
      (node (ref "U$4") (pin "1") (pinfunction "R4_1") (pintype "bidirectional"))
      (node (ref "U$5") (pin "1") (pinfunction "R4_1") (pintype "bidirectional"))
      (node (ref "U$6") (pin "1") (pinfunction "R4_1") (pintype "bidirectional"))
    )
    (net (code "103") (name "Net-(IC10-O6)") (class "Default")
      (node (ref "IC10") (pin "13") (pinfunction "O6_13") (pintype "open_collector"))
      (node (ref "U$4") (pin "7") (pinfunction "R5_7") (pintype "bidirectional"))
      (node (ref "U$5") (pin "7") (pinfunction "R5_7") (pintype "bidirectional"))
      (node (ref "U$6") (pin "7") (pinfunction "R5_7") (pintype "bidirectional"))
    )
    (net (code "104") (name "Net-(IC10-O7)") (class "Default")
      (node (ref "IC10") (pin "12") (pinfunction "O7_12") (pintype "open_collector"))
      (node (ref "U$4") (pin "2") (pinfunction "R6_2") (pintype "bidirectional"))
      (node (ref "U$5") (pin "2") (pinfunction "R6_2") (pintype "bidirectional"))
      (node (ref "U$6") (pin "2") (pinfunction "R6_2") (pintype "bidirectional"))
    )
    (net (code "105") (name "Net-(IC10-O8)") (class "Default")
      (node (ref "IC10") (pin "11") (pinfunction "O8_11") (pintype "open_collector"))
      (node (ref "U$4") (pin "5") (pinfunction "R8_5") (pintype "bidirectional"))
      (node (ref "U$5") (pin "5") (pinfunction "R8_5") (pintype "bidirectional"))
      (node (ref "U$6") (pin "5") (pinfunction "R8_5") (pintype "bidirectional"))
    )
    (net (code "106") (name "Net-(IC11A-QA)") (class "Default")
      (node (ref "IC11") (pin "15") (pinfunction "QA_15") (pintype "tri_state"))
      (node (ref "IC12") (pin "1") (pinfunction "I1_1") (pintype "input"))
    )
    (net (code "107") (name "Net-(IC11A-QB)") (class "Default")
      (node (ref "IC11") (pin "1") (pinfunction "QB_1") (pintype "tri_state"))
      (node (ref "IC12") (pin "2") (pinfunction "I2_2") (pintype "input"))
    )
    (net (code "108") (name "Net-(IC11A-QC)") (class "Default")
      (node (ref "IC11") (pin "2") (pinfunction "QC_2") (pintype "tri_state"))
      (node (ref "IC12") (pin "3") (pinfunction "I3_3") (pintype "input"))
    )
    (net (code "109") (name "Net-(IC11A-QD)") (class "Default")
      (node (ref "IC11") (pin "3") (pinfunction "QD_3") (pintype "tri_state"))
      (node (ref "IC12") (pin "4") (pinfunction "I4_4") (pintype "input"))
    )
    (net (code "110") (name "Net-(IC11A-QE)") (class "Default")
      (node (ref "IC11") (pin "4") (pinfunction "QE_4") (pintype "tri_state"))
      (node (ref "IC12") (pin "5") (pinfunction "I5_5") (pintype "input"))
    )
    (net (code "111") (name "Net-(IC11A-QF)") (class "Default")
      (node (ref "IC11") (pin "5") (pinfunction "QF_5") (pintype "tri_state"))
      (node (ref "IC12") (pin "6") (pinfunction "I6_6") (pintype "input"))
    )
    (net (code "112") (name "Net-(IC11A-QG)") (class "Default")
      (node (ref "IC11") (pin "6") (pinfunction "QG_6") (pintype "tri_state"))
      (node (ref "IC12") (pin "7") (pinfunction "I7_7") (pintype "input"))
    )
    (net (code "113") (name "Net-(IC11A-QH)") (class "Default")
      (node (ref "IC11") (pin "7") (pinfunction "QH_7") (pintype "tri_state"))
      (node (ref "IC12") (pin "8") (pinfunction "I8_8") (pintype "input"))
    )
    (net (code "114") (name "Net-(IC11A-SER)") (class "Default")
      (node (ref "IC11") (pin "14") (pinfunction "SER_14") (pintype "input"))
      (node (ref "IC9") (pin "9") (pinfunction "QH*_9") (pintype "tri_state"))
    )
    (net (code "115") (name "Net-(IC12-O1)") (class "Default")
      (node (ref "IC12") (pin "18") (pinfunction "O1_18") (pintype "open_collector"))
      (node (ref "U$7") (pin "9") (pinfunction "R0_9") (pintype "bidirectional"))
      (node (ref "U$8") (pin "9") (pinfunction "R0_9") (pintype "bidirectional"))
      (node (ref "U$9") (pin "9") (pinfunction "R0_9") (pintype "bidirectional"))
    )
    (net (code "116") (name "Net-(IC12-O2)") (class "Default")
      (node (ref "IC12") (pin "17") (pinfunction "O2_17") (pintype "open_collector"))
      (node (ref "U$7") (pin "14") (pinfunction "R1_14") (pintype "bidirectional"))
      (node (ref "U$8") (pin "14") (pinfunction "R1_14") (pintype "bidirectional"))
      (node (ref "U$9") (pin "14") (pinfunction "R1_14") (pintype "bidirectional"))
    )
    (net (code "117") (name "Net-(IC12-O3)") (class "Default")
      (node (ref "IC12") (pin "16") (pinfunction "O3_16") (pintype "open_collector"))
      (node (ref "U$7") (pin "8") (pinfunction "R2_8") (pintype "bidirectional"))
      (node (ref "U$8") (pin "8") (pinfunction "R2_8") (pintype "bidirectional"))
      (node (ref "U$9") (pin "8") (pinfunction "R2_8") (pintype "bidirectional"))
    )
    (net (code "118") (name "Net-(IC12-O4)") (class "Default")
      (node (ref "IC12") (pin "15") (pinfunction "O4_15") (pintype "open_collector"))
      (node (ref "U$7") (pin "12") (pinfunction "R3_12") (pintype "bidirectional"))
      (node (ref "U$8") (pin "12") (pinfunction "R3_12") (pintype "bidirectional"))
      (node (ref "U$9") (pin "12") (pinfunction "R3_12") (pintype "bidirectional"))
    )
    (net (code "119") (name "Net-(IC12-O5)") (class "Default")
      (node (ref "IC12") (pin "14") (pinfunction "O5_14") (pintype "open_collector"))
      (node (ref "U$7") (pin "1") (pinfunction "R4_1") (pintype "bidirectional"))
      (node (ref "U$8") (pin "1") (pinfunction "R4_1") (pintype "bidirectional"))
      (node (ref "U$9") (pin "1") (pinfunction "R4_1") (pintype "bidirectional"))
    )
    (net (code "120") (name "Net-(IC12-O6)") (class "Default")
      (node (ref "IC12") (pin "13") (pinfunction "O6_13") (pintype "open_collector"))
      (node (ref "U$7") (pin "7") (pinfunction "R5_7") (pintype "bidirectional"))
      (node (ref "U$8") (pin "7") (pinfunction "R5_7") (pintype "bidirectional"))
      (node (ref "U$9") (pin "7") (pinfunction "R5_7") (pintype "bidirectional"))
    )
    (net (code "121") (name "Net-(IC12-O7)") (class "Default")
      (node (ref "IC12") (pin "12") (pinfunction "O7_12") (pintype "open_collector"))
      (node (ref "U$7") (pin "2") (pinfunction "R6_2") (pintype "bidirectional"))
      (node (ref "U$8") (pin "2") (pinfunction "R6_2") (pintype "bidirectional"))
      (node (ref "U$9") (pin "2") (pinfunction "R6_2") (pintype "bidirectional"))
    )
    (net (code "122") (name "Net-(IC12-O8)") (class "Default")
      (node (ref "IC12") (pin "11") (pinfunction "O8_11") (pintype "open_collector"))
      (node (ref "U$7") (pin "5") (pinfunction "R8_5") (pintype "bidirectional"))
      (node (ref "U$8") (pin "5") (pinfunction "R8_5") (pintype "bidirectional"))
      (node (ref "U$9") (pin "5") (pinfunction "R8_5") (pintype "bidirectional"))
    )
    (net (code "123") (name "Net-(S1-P1)") (class "Default")
      (node (ref "R16") (pin "1") (pinfunction "1_1") (pintype "passive"))
      (node (ref "S1") (pin "4") (pinfunction "P1_4") (pintype "passive"))
    )
    (net (code "124") (name "Net-(S1-S)") (class "Default")
      (node (ref "R15") (pin "1") (pinfunction "1_1") (pintype "passive"))
      (node (ref "S1") (pin "1") (pinfunction "S_1") (pintype "passive"))
    )
    (net (code "125") (name "Net-(S1-S1)") (class "Default")
      (node (ref "C1") (pin "2") (pinfunction "2_2") (pintype "passive"))
      (node (ref "R17") (pin "1") (pinfunction "1_1") (pintype "passive"))
      (node (ref "S1") (pin "2") (pinfunction "S1_2") (pintype "passive"))
    )
    (net (code "126") (name "Net-(S2-P1)") (class "Default")
      (node (ref "R19") (pin "2") (pinfunction "2_2") (pintype "passive"))
      (node (ref "S2") (pin "4") (pinfunction "P1_4") (pintype "passive"))
    )
    (net (code "127") (name "Net-(S2-S)") (class "Default")
      (node (ref "R18") (pin "2") (pinfunction "2_2") (pintype "passive"))
      (node (ref "S2") (pin "1") (pinfunction "S_1") (pintype "passive"))
    )
    (net (code "128") (name "Net-(S2-S1)") (class "Default")
      (node (ref "C2") (pin "2") (pinfunction "2_2") (pintype "passive"))
      (node (ref "R20") (pin "1") (pinfunction "1_1") (pintype "passive"))
      (node (ref "S2") (pin "2") (pinfunction "S1_2") (pintype "passive"))
    )
    (net (code "129") (name "Net-(S3-P1)") (class "Default")
      (node (ref "R22") (pin "1") (pinfunction "1_1") (pintype "passive"))
      (node (ref "S3") (pin "4") (pinfunction "P1_4") (pintype "passive"))
    )
    (net (code "130") (name "Net-(S3-S)") (class "Default")
      (node (ref "R21") (pin "1") (pinfunction "1_1") (pintype "passive"))
      (node (ref "S3") (pin "1") (pinfunction "S_1") (pintype "passive"))
    )
    (net (code "131") (name "Net-(S3-S1)") (class "Default")
      (node (ref "C3") (pin "2") (pinfunction "2_2") (pintype "passive"))
      (node (ref "R23") (pin "1") (pinfunction "1_1") (pintype "passive"))
      (node (ref "S3") (pin "2") (pinfunction "S1_2") (pintype "passive"))
    )
    (net (code "132") (name "Net-(S4-P1)") (class "Default")
      (node (ref "R25") (pin "2") (pinfunction "2_2") (pintype "passive"))
      (node (ref "S4") (pin "4") (pinfunction "P1_4") (pintype "passive"))
    )
    (net (code "133") (name "Net-(S4-S)") (class "Default")
      (node (ref "R24") (pin "2") (pinfunction "2_2") (pintype "passive"))
      (node (ref "S4") (pin "1") (pinfunction "S_1") (pintype "passive"))
    )
    (net (code "134") (name "Net-(S4-S1)") (class "Default")
      (node (ref "C4") (pin "2") (pinfunction "2_2") (pintype "passive"))
      (node (ref "R26") (pin "1") (pinfunction "1_1") (pintype "passive"))
      (node (ref "S4") (pin "2") (pinfunction "S1_2") (pintype "passive"))
    )
    (net (code "135") (name "Net-(S5-P1)") (class "Default")
      (node (ref "R38") (pin "1") (pinfunction "1_1") (pintype "passive"))
      (node (ref "S5") (pin "4") (pinfunction "P1_4") (pintype "passive"))
    )
    (net (code "136") (name "Net-(S5-S)") (class "Default")
      (node (ref "R37") (pin "1") (pinfunction "1_1") (pintype "passive"))
      (node (ref "S5") (pin "1") (pinfunction "S_1") (pintype "passive"))
    )
    (net (code "137") (name "Net-(S5-S1)") (class "Default")
      (node (ref "C5") (pin "2") (pinfunction "2_2") (pintype "passive"))
      (node (ref "R39") (pin "1") (pinfunction "1_1") (pintype "passive"))
      (node (ref "S5") (pin "2") (pinfunction "S1_2") (pintype "passive"))
    )
    (net (code "138") (name "Net-(S6-P1)") (class "Default")
      (node (ref "R41") (pin "2") (pinfunction "2_2") (pintype "passive"))
      (node (ref "S6") (pin "4") (pinfunction "P1_4") (pintype "passive"))
    )
    (net (code "139") (name "Net-(S6-S)") (class "Default")
      (node (ref "R40") (pin "2") (pinfunction "2_2") (pintype "passive"))
      (node (ref "S6") (pin "1") (pinfunction "S_1") (pintype "passive"))
    )
    (net (code "140") (name "Net-(S6-S1)") (class "Default")
      (node (ref "C6") (pin "2") (pinfunction "2_2") (pintype "passive"))
      (node (ref "R42") (pin "1") (pinfunction "1_1") (pintype "passive"))
      (node (ref "S6") (pin "2") (pinfunction "S1_2") (pintype "passive"))
    )
    (net (code "141") (name "Net-(S7-P1)") (class "Default")
      (node (ref "R44") (pin "1") (pinfunction "1_1") (pintype "passive"))
      (node (ref "S7") (pin "4") (pinfunction "P1_4") (pintype "passive"))
    )
    (net (code "142") (name "Net-(S7-S)") (class "Default")
      (node (ref "R43") (pin "1") (pinfunction "1_1") (pintype "passive"))
      (node (ref "S7") (pin "1") (pinfunction "S_1") (pintype "passive"))
    )
    (net (code "143") (name "Net-(S7-S1)") (class "Default")
      (node (ref "C7") (pin "2") (pinfunction "2_2") (pintype "passive"))
      (node (ref "R45") (pin "1") (pinfunction "1_1") (pintype "passive"))
      (node (ref "S7") (pin "2") (pinfunction "S1_2") (pintype "passive"))
    )
    (net (code "144") (name "Net-(S8-P1)") (class "Default")
      (node (ref "R47") (pin "2") (pinfunction "2_2") (pintype "passive"))
      (node (ref "S8") (pin "4") (pinfunction "P1_4") (pintype "passive"))
    )
    (net (code "145") (name "Net-(S8-S)") (class "Default")
      (node (ref "R46") (pin "2") (pinfunction "2_2") (pintype "passive"))
      (node (ref "S8") (pin "1") (pinfunction "S_1") (pintype "passive"))
    )
    (net (code "146") (name "Net-(S8-S1)") (class "Default")
      (node (ref "C8") (pin "2") (pinfunction "2_2") (pintype "passive"))
      (node (ref "R48") (pin "1") (pinfunction "1_1") (pintype "passive"))
      (node (ref "S8") (pin "2") (pinfunction "S1_2") (pintype "passive"))
    )
    (net (code "147") (name "Net-(U$1-C2)") (class "Default")
      (node (ref "R3") (pin "2") (pinfunction "2_2") (pintype "passive"))
      (node (ref "U$1") (pin "4") (pinfunction "C2_4") (pintype "bidirectional"))
      (node (ref "U$4") (pin "4") (pinfunction "C2_4") (pintype "bidirectional"))
      (node (ref "U$7") (pin "4") (pinfunction "C2_4") (pintype "bidirectional"))
    )
    (net (code "148") (name "Net-(U$1-C3)") (class "Default")
      (node (ref "R4") (pin "1") (pinfunction "1_1") (pintype "passive"))
      (node (ref "U$1") (pin "10") (pinfunction "C3_10") (pintype "bidirectional"))
      (node (ref "U$4") (pin "10") (pinfunction "C3_10") (pintype "bidirectional"))
      (node (ref "U$7") (pin "10") (pinfunction "C3_10") (pintype "bidirectional"))
    )
    (net (code "149") (name "Net-(U$1-C4)") (class "Default")
      (node (ref "R5") (pin "2") (pinfunction "2_2") (pintype "passive"))
      (node (ref "U$1") (pin "6") (pinfunction "C4_6") (pintype "bidirectional"))
      (node (ref "U$4") (pin "6") (pinfunction "C4_6") (pintype "bidirectional"))
      (node (ref "U$7") (pin "6") (pinfunction "C4_6") (pintype "bidirectional"))
    )
    (net (code "150") (name "Net-(U$1-C5)") (class "Default")
      (node (ref "R6") (pin "1") (pinfunction "1_1") (pintype "passive"))
      (node (ref "U$1") (pin "11") (pinfunction "C5_11") (pintype "bidirectional"))
      (node (ref "U$4") (pin "11") (pinfunction "C5_11") (pintype "bidirectional"))
      (node (ref "U$7") (pin "11") (pinfunction "C5_11") (pintype "bidirectional"))
    )
    (net (code "151") (name "Net-(U$1-C6)") (class "Default")
      (node (ref "R7") (pin "2") (pinfunction "2_2") (pintype "passive"))
      (node (ref "U$1") (pin "15") (pinfunction "C6_15") (pintype "bidirectional"))
      (node (ref "U$4") (pin "15") (pinfunction "C6_15") (pintype "bidirectional"))
      (node (ref "U$7") (pin "15") (pinfunction "C6_15") (pintype "bidirectional"))
    )
    (net (code "152") (name "Net-(U$1-C7)") (class "Default")
      (node (ref "R8") (pin "1") (pinfunction "1_1") (pintype "passive"))
      (node (ref "U$1") (pin "16") (pinfunction "C7_16") (pintype "bidirectional"))
      (node (ref "U$4") (pin "16") (pinfunction "C7_16") (pintype "bidirectional"))
      (node (ref "U$7") (pin "16") (pinfunction "C7_16") (pintype "bidirectional"))
    )
    (net (code "153") (name "Net-(U$2-C0)") (class "Default")
      (node (ref "R9") (pin "2") (pinfunction "2_2") (pintype "passive"))
      (node (ref "U$2") (pin "13") (pinfunction "C0_13") (pintype "bidirectional"))
      (node (ref "U$5") (pin "13") (pinfunction "C0_13") (pintype "bidirectional"))
      (node (ref "U$8") (pin "13") (pinfunction "C0_13") (pintype "bidirectional"))
    )
    (net (code "154") (name "Net-(U$2-C1)") (class "Default")
      (node (ref "R10") (pin "1") (pinfunction "1_1") (pintype "passive"))
      (node (ref "U$2") (pin "3") (pinfunction "C1_3") (pintype "bidirectional"))
      (node (ref "U$5") (pin "3") (pinfunction "C1_3") (pintype "bidirectional"))
      (node (ref "U$8") (pin "3") (pinfunction "C1_3") (pintype "bidirectional"))
    )
    (net (code "155") (name "Net-(U$2-C2)") (class "Default")
      (node (ref "R11") (pin "2") (pinfunction "2_2") (pintype "passive"))
      (node (ref "U$2") (pin "4") (pinfunction "C2_4") (pintype "bidirectional"))
      (node (ref "U$5") (pin "4") (pinfunction "C2_4") (pintype "bidirectional"))
      (node (ref "U$8") (pin "4") (pinfunction "C2_4") (pintype "bidirectional"))
    )
    (net (code "156") (name "Net-(U$2-C3)") (class "Default")
      (node (ref "R12") (pin "1") (pinfunction "1_1") (pintype "passive"))
      (node (ref "U$2") (pin "10") (pinfunction "C3_10") (pintype "bidirectional"))
      (node (ref "U$5") (pin "10") (pinfunction "C3_10") (pintype "bidirectional"))
      (node (ref "U$8") (pin "10") (pinfunction "C3_10") (pintype "bidirectional"))
    )
    (net (code "157") (name "Net-(U$2-C4)") (class "Default")
      (node (ref "R13") (pin "2") (pinfunction "2_2") (pintype "passive"))
      (node (ref "U$2") (pin "6") (pinfunction "C4_6") (pintype "bidirectional"))
      (node (ref "U$5") (pin "6") (pinfunction "C4_6") (pintype "bidirectional"))
      (node (ref "U$8") (pin "6") (pinfunction "C4_6") (pintype "bidirectional"))
    )
    (net (code "158") (name "Net-(U$2-C5)") (class "Default")
      (node (ref "R14") (pin "1") (pinfunction "1_1") (pintype "passive"))
      (node (ref "U$2") (pin "11") (pinfunction "C5_11") (pintype "bidirectional"))
      (node (ref "U$5") (pin "11") (pinfunction "C5_11") (pintype "bidirectional"))
      (node (ref "U$8") (pin "11") (pinfunction "C5_11") (pintype "bidirectional"))
    )
    (net (code "159") (name "Net-(U$2-C6)") (class "Default")
      (node (ref "R27") (pin "1") (pinfunction "1_1") (pintype "passive"))
      (node (ref "U$2") (pin "15") (pinfunction "C6_15") (pintype "bidirectional"))
      (node (ref "U$5") (pin "15") (pinfunction "C6_15") (pintype "bidirectional"))
      (node (ref "U$8") (pin "15") (pinfunction "C6_15") (pintype "bidirectional"))
    )
    (net (code "160") (name "Net-(U$2-C7)") (class "Default")
      (node (ref "R28") (pin "1") (pinfunction "1_1") (pintype "passive"))
      (node (ref "U$2") (pin "16") (pinfunction "C7_16") (pintype "bidirectional"))
      (node (ref "U$5") (pin "16") (pinfunction "C7_16") (pintype "bidirectional"))
      (node (ref "U$8") (pin "16") (pinfunction "C7_16") (pintype "bidirectional"))
    )
    (net (code "161") (name "Net-(U$3-C0)") (class "Default")
      (node (ref "R29") (pin "2") (pinfunction "2_2") (pintype "passive"))
      (node (ref "U$3") (pin "13") (pinfunction "C0_13") (pintype "bidirectional"))
      (node (ref "U$6") (pin "13") (pinfunction "C0_13") (pintype "bidirectional"))
      (node (ref "U$9") (pin "13") (pinfunction "C0_13") (pintype "bidirectional"))
    )
    (net (code "162") (name "Net-(U$3-C1)") (class "Default")
      (node (ref "R30") (pin "1") (pinfunction "1_1") (pintype "passive"))
      (node (ref "U$3") (pin "3") (pinfunction "C1_3") (pintype "bidirectional"))
      (node (ref "U$6") (pin "3") (pinfunction "C1_3") (pintype "bidirectional"))
      (node (ref "U$9") (pin "3") (pinfunction "C1_3") (pintype "bidirectional"))
    )
    (net (code "163") (name "Net-(U$3-C2)") (class "Default")
      (node (ref "R31") (pin "2") (pinfunction "2_2") (pintype "passive"))
      (node (ref "U$3") (pin "4") (pinfunction "C2_4") (pintype "bidirectional"))
      (node (ref "U$6") (pin "4") (pinfunction "C2_4") (pintype "bidirectional"))
      (node (ref "U$9") (pin "4") (pinfunction "C2_4") (pintype "bidirectional"))
    )
    (net (code "164") (name "Net-(U$3-C3)") (class "Default")
      (node (ref "R32") (pin "1") (pinfunction "1_1") (pintype "passive"))
      (node (ref "U$3") (pin "10") (pinfunction "C3_10") (pintype "bidirectional"))
      (node (ref "U$6") (pin "10") (pinfunction "C3_10") (pintype "bidirectional"))
      (node (ref "U$9") (pin "10") (pinfunction "C3_10") (pintype "bidirectional"))
    )
    (net (code "165") (name "Net-(U$3-C4)") (class "Default")
      (node (ref "R33") (pin "2") (pinfunction "2_2") (pintype "passive"))
      (node (ref "U$3") (pin "6") (pinfunction "C4_6") (pintype "bidirectional"))
      (node (ref "U$6") (pin "6") (pinfunction "C4_6") (pintype "bidirectional"))
      (node (ref "U$9") (pin "6") (pinfunction "C4_6") (pintype "bidirectional"))
    )
    (net (code "166") (name "Net-(U$3-C5)") (class "Default")
      (node (ref "R34") (pin "1") (pinfunction "1_1") (pintype "passive"))
      (node (ref "U$3") (pin "11") (pinfunction "C5_11") (pintype "bidirectional"))
      (node (ref "U$6") (pin "11") (pinfunction "C5_11") (pintype "bidirectional"))
      (node (ref "U$9") (pin "11") (pinfunction "C5_11") (pintype "bidirectional"))
    )
    (net (code "167") (name "Net-(U$3-C6)") (class "Default")
      (node (ref "R35") (pin "1") (pinfunction "1_1") (pintype "passive"))
      (node (ref "U$3") (pin "15") (pinfunction "C6_15") (pintype "bidirectional"))
      (node (ref "U$6") (pin "15") (pinfunction "C6_15") (pintype "bidirectional"))
      (node (ref "U$9") (pin "15") (pinfunction "C6_15") (pintype "bidirectional"))
    )
    (net (code "168") (name "Net-(U$3-C7)") (class "Default")
      (node (ref "R36") (pin "1") (pinfunction "1_1") (pintype "passive"))
      (node (ref "U$3") (pin "16") (pinfunction "C7_16") (pintype "bidirectional"))
      (node (ref "U$6") (pin "16") (pinfunction "C7_16") (pintype "bidirectional"))
      (node (ref "U$9") (pin "16") (pinfunction "C7_16") (pintype "bidirectional"))
    )
    (net (code "169") (name "SR-G") (class "Default")
      (node (ref "IC1") (pin "13") (pinfunction "G_13") (pintype "input"))
      (node (ref "IC11") (pin "13") (pinfunction "G_13") (pintype "input"))
      (node (ref "IC2") (pin "13") (pinfunction "G_13") (pintype "input"))
      (node (ref "IC3") (pin "13") (pinfunction "G_13") (pintype "input"))
      (node (ref "IC6") (pin "13") (pinfunction "G_13") (pintype "input"))
      (node (ref "IC9") (pin "13") (pinfunction "G_13") (pintype "input"))
    )
    (net (code "170") (name "SR-RCK") (class "Default")
      (node (ref "IC1") (pin "12") (pinfunction "RCK_12") (pintype "input"))
      (node (ref "IC11") (pin "12") (pinfunction "RCK_12") (pintype "input"))
      (node (ref "IC2") (pin "12") (pinfunction "RCK_12") (pintype "input"))
      (node (ref "IC3") (pin "12") (pinfunction "RCK_12") (pintype "input"))
      (node (ref "IC6") (pin "12") (pinfunction "RCK_12") (pintype "input"))
      (node (ref "IC9") (pin "12") (pinfunction "RCK_12") (pintype "input"))
    )
    (net (code "171") (name "SR-SCK") (class "Default")
      (node (ref "IC1") (pin "11") (pinfunction "SCK_11") (pintype "input"))
      (node (ref "IC11") (pin "11") (pinfunction "SCK_11") (pintype "input"))
      (node (ref "IC2") (pin "11") (pinfunction "SCK_11") (pintype "input"))
      (node (ref "IC3") (pin "11") (pinfunction "SCK_11") (pintype "input"))
      (node (ref "IC6") (pin "11") (pinfunction "SCK_11") (pintype "input"))
      (node (ref "IC9") (pin "11") (pinfunction "SCK_11") (pintype "input"))
    )
    (net (code "172") (name "SR-SCL") (class "Default")
      (node (ref "IC1") (pin "10") (pinfunction "SCL_10") (pintype "input"))
      (node (ref "IC11") (pin "10") (pinfunction "SCL_10") (pintype "input"))
      (node (ref "IC2") (pin "10") (pinfunction "SCL_10") (pintype "input"))
      (node (ref "IC3") (pin "10") (pinfunction "SCL_10") (pintype "input"))
      (node (ref "IC6") (pin "10") (pinfunction "SCL_10") (pintype "input"))
      (node (ref "IC9") (pin "10") (pinfunction "SCL_10") (pintype "input"))
    )
    (net (code "173") (name "SR-SER") (class "Default")
      (node (ref "IC6") (pin "14") (pinfunction "SER_14") (pintype "input"))
    )
    (net (code "174") (name "unconnected-(IC7-CD+-Pad10)") (class "Default")
      (node (ref "IC7") (pin "10") (pinfunction "CD+_10") (pintype "passive"))
    )
    (net (code "175") (name "unconnected-(IC10-CD+-Pad10)") (class "Default")
      (node (ref "IC10") (pin "10") (pinfunction "CD+_10") (pintype "passive"))
    )
    (net (code "176") (name "unconnected-(IC11A-QH*-Pad9)") (class "Default")
      (node (ref "IC11") (pin "9") (pinfunction "QH*_9") (pintype "tri_state"))
    )
    (net (code "177") (name "unconnected-(IC12-CD+-Pad10)") (class "Default")
      (node (ref "IC12") (pin "10") (pinfunction "CD+_10") (pintype "passive"))
    )
    (net (code "178") (name "unconnected-(LED1-A-Pad4)") (class "Default")
      (node (ref "LED1") (pin "4") (pinfunction "A_4") (pintype "passive"))
    )
    (net (code "179") (name "unconnected-(LED1-CBLUE-Pad3)") (class "Default")
      (node (ref "LED1") (pin "3") (pinfunction "CBLUE_3") (pintype "passive"))
    )
    (net (code "180") (name "unconnected-(LED1-CGREEN-Pad1)") (class "Default")
      (node (ref "LED1") (pin "1") (pinfunction "CGREEN_1") (pintype "passive"))
    )
    (net (code "181") (name "unconnected-(LED1-CRED-Pad2)") (class "Default")
      (node (ref "LED1") (pin "2") (pinfunction "CRED_2") (pintype "passive"))
    )
    (net (code "182") (name "unconnected-(PCB1-(N{slash}C)-PadN{slash}C)") (class "Default")
      (node (ref "PCB1") (pin "N/C") (pinfunction "(N/C)_N/C") (pintype "bidirectional"))
    )
    (net (code "183") (name "unconnected-(PCB1-0(RX)-Pad0)") (class "Default")
      (node (ref "PCB1") (pin "0") (pinfunction "0(RX)_0") (pintype "bidirectional"))
    )
    (net (code "184") (name "unconnected-(PCB1-1(TX)-Pad1)") (class "Default")
      (node (ref "PCB1") (pin "1") (pinfunction "1(TX)_1") (pintype "bidirectional"))
    )
    (net (code "185") (name "unconnected-(PCB1-27(SDA)-PadSDA)") (class "Default")
      (node (ref "PCB1") (pin "SDA") (pinfunction "27(SDA)_SDA") (pintype "bidirectional"))
    )
    (net (code "186") (name "unconnected-(PCB1-28(SCL)-PadSCL)") (class "Default")
      (node (ref "PCB1") (pin "SCL") (pinfunction "28(SCL)_SCL") (pintype "bidirectional"))
    )
    (net (code "187") (name "unconnected-(PCB1-IOREF-PadI{slash}OREF)") (class "Default")
      (node (ref "PCB1") (pin "I/OREF") (pinfunction "IOREF_I/OREF") (pintype "bidirectional"))
    )
    (net (code "188") (name "unconnected-(PCB1-Pad+5V)") (class "Default")
      (node (ref "PCB1") (pin "+5V") (pinfunction "+5V_+5V") (pintype "bidirectional"))
    )
    (net (code "189") (name "unconnected-(PCB1-Pad2)") (class "Default")
      (node (ref "PCB1") (pin "2") (pinfunction "2_2") (pintype "bidirectional"))
    )
    (net (code "190") (name "unconnected-(PCB1-Pad3.3V)") (class "Default")
      (node (ref "PCB1") (pin "3.3V") (pinfunction "3.3V_3.3V") (pintype "bidirectional"))
    )
    (net (code "191") (name "unconnected-(PCB1-Pad4)") (class "Default")
      (node (ref "PCB1") (pin "4") (pinfunction "4_4") (pintype "bidirectional"))
    )
    (net (code "192") (name "unconnected-(PCB1-Pad5V)") (class "Default")
      (node (ref "PCB1") (pin "5V") (pinfunction "5V_5V") (pintype "bidirectional"))
    )
    (net (code "193") (name "unconnected-(PCB1-Pad7)") (class "Default")
      (node (ref "PCB1") (pin "7") (pinfunction "7_7") (pintype "bidirectional"))
    )
    (net (code "194") (name "unconnected-(PCB1-Pad8)") (class "Default")
      (node (ref "PCB1") (pin "8") (pinfunction "8_8") (pintype "bidirectional"))
    )
    (net (code "195") (name "unconnected-(PCB1-Pad12)") (class "Default")
      (node (ref "PCB1") (pin "12") (pinfunction "12_12") (pintype "bidirectional"))
    )
    (net (code "196") (name "unconnected-(PCB1-Pad13)") (class "Default")
      (node (ref "PCB1") (pin "13") (pinfunction "13_13") (pintype "bidirectional"))
    )
    (net (code "197") (name "unconnected-(PCB1-Pad<PWR>+V)") (class "Default")
      (node (ref "PCB1") (pin "<PWR>+V") (pinfunction "<PWR>+V_<PWR>+V") (pintype "bidirectional"))
    )
    (net (code "198") (name "unconnected-(PCB1-Pad<PWR>-V)") (class "Default")
      (node (ref "PCB1") (pin "<PWR>-V") (pinfunction "<PWR>-V_<PWR>-V") (pintype "bidirectional"))
    )
    (net (code "199") (name "unconnected-(PCB1-Pad<USB>+V)") (class "Default")
      (node (ref "PCB1") (pin "<USB>+V") (pinfunction "<USB>+V_<USB>+V") (pintype "bidirectional"))
    )
    (net (code "200") (name "unconnected-(PCB1-Pad<USB>D+)") (class "Default")
      (node (ref "PCB1") (pin "<USB>D+") (pinfunction "<USB>D+_<USB>D+") (pintype "bidirectional"))
    )
    (net (code "201") (name "unconnected-(PCB1-Pad<USB>D-)") (class "Default")
      (node (ref "PCB1") (pin "<USB>D-") (pinfunction "<USB>D-_<USB>D-") (pintype "bidirectional"))
    )
    (net (code "202") (name "unconnected-(PCB1-Pad<USB>GND)") (class "Default")
      (node (ref "PCB1") (pin "<USB>GND") (pinfunction "<USB>GND_<USB>GND") (pintype "bidirectional"))
    )
    (net (code "203") (name "unconnected-(PCB1-PadA0)") (class "Default")
      (node (ref "PCB1") (pin "A0") (pinfunction "A0_A0") (pintype "bidirectional"))
    )
    (net (code "204") (name "unconnected-(PCB1-PadA1)") (class "Default")
      (node (ref "PCB1") (pin "A1") (pinfunction "A1_A1") (pintype "bidirectional"))
    )
    (net (code "205") (name "unconnected-(PCB1-PadA2)") (class "Default")
      (node (ref "PCB1") (pin "A2") (pinfunction "A2_A2") (pintype "bidirectional"))
    )
    (net (code "206") (name "unconnected-(PCB1-PadA3)") (class "Default")
      (node (ref "PCB1") (pin "A3") (pinfunction "A3_A3") (pintype "bidirectional"))
    )
    (net (code "207") (name "unconnected-(PCB1-PadA4)") (class "Default")
      (node (ref "PCB1") (pin "A4") (pinfunction "A4_A4") (pintype "bidirectional"))
    )
    (net (code "208") (name "unconnected-(PCB1-PadA5)") (class "Default")
      (node (ref "PCB1") (pin "A5") (pinfunction "A5_A5") (pintype "bidirectional"))
    )
    (net (code "209") (name "unconnected-(PCB1-PadAREF)") (class "Default")
      (node (ref "PCB1") (pin "AREF") (pinfunction "AREF_AREF") (pintype "bidirectional"))
    )
    (net (code "210") (name "unconnected-(PCB1-PadGND)") (class "Default")
      (node (ref "PCB1") (pin "GND") (pinfunction "GND_GND") (pintype "bidirectional"))
    )
    (net (code "211") (name "unconnected-(PCB1-PadGND.)") (class "Default")
      (node (ref "PCB1") (pin "GND.") (pinfunction "GND._GND.") (pintype "bidirectional"))
    )
    (net (code "212") (name "unconnected-(PCB1-PadGND..)") (class "Default")
      (node (ref "PCB1") (pin "GND..") (pinfunction "GND.._GND..") (pintype "bidirectional"))
    )
    (net (code "213") (name "unconnected-(PCB1-PadGND_)") (class "Default")
      (node (ref "PCB1") (pin "GND_") (pinfunction "GND__GND_") (pintype "bidirectional"))
    )
    (net (code "214") (name "unconnected-(PCB1-PadMISO)") (class "Default")
      (node (ref "PCB1") (pin "MISO") (pinfunction "MISO_MISO") (pintype "bidirectional"))
    )
    (net (code "215") (name "unconnected-(PCB1-PadMOSI)") (class "Default")
      (node (ref "PCB1") (pin "MOSI") (pinfunction "MOSI_MOSI") (pintype "bidirectional"))
    )
    (net (code "216") (name "unconnected-(PCB1-PadRESET)") (class "Default")
      (node (ref "PCB1") (pin "RESET") (pinfunction "RESET_RESET") (pintype "bidirectional"))
    )
    (net (code "217") (name "unconnected-(PCB1-PadRESET.)") (class "Default")
      (node (ref "PCB1") (pin "RESET.") (pinfunction "RESET._RESET.") (pintype "bidirectional"))
    )
    (net (code "218") (name "unconnected-(PCB1-PadSCK)") (class "Default")
      (node (ref "PCB1") (pin "SCK") (pinfunction "SCK_SCK") (pintype "bidirectional"))
    )
    (net (code "219") (name "unconnected-(PCB1-PadVIN)") (class "Default")
      (node (ref "PCB1") (pin "VIN") (pinfunction "VIN_VIN") (pintype "bidirectional"))
    )
    (net (code "220") (name "unconnected-(PCB1-~{3}-Pad3)") (class "Default")
      (node (ref "PCB1") (pin "3") (pinfunction "~{3}_3") (pintype "bidirectional"))
    )
    (net (code "221") (name "unconnected-(PCB1-~{5}-Pad5)") (class "Default")
      (node (ref "PCB1") (pin "5") (pinfunction "~{5}_5") (pintype "bidirectional"))
    )
    (net (code "222") (name "unconnected-(PCB1-~{6}-Pad6)") (class "Default")
      (node (ref "PCB1") (pin "6") (pinfunction "~{6}_6") (pintype "bidirectional"))
    )
    (net (code "223") (name "unconnected-(PCB1-~{9}-Pad9)") (class "Default")
      (node (ref "PCB1") (pin "9") (pinfunction "~{9}_9") (pintype "bidirectional"))
    )
    (net (code "224") (name "unconnected-(PCB1-~{10}-Pad10)") (class "Default")
      (node (ref "PCB1") (pin "10") (pinfunction "~{10}_10") (pintype "bidirectional"))
    )
    (net (code "225") (name "unconnected-(PCB1-~{11}-Pad11)") (class "Default")
      (node (ref "PCB1") (pin "11") (pinfunction "~{11}_11") (pintype "bidirectional"))
    )
    (net (code "226") (name "unconnected-(SP1-Pad1)") (class "Default")
      (node (ref "SP1") (pin "1") (pinfunction "1_1") (pintype "passive"))
    )
    (net (code "227") (name "unconnected-(SP1-Pad2)") (class "Default")
      (node (ref "SP1") (pin "2") (pinfunction "2_2") (pintype "passive"))
    )
  )
)
